# GCharger.net
KiCad netlist of a schematic drawn in EAGLE
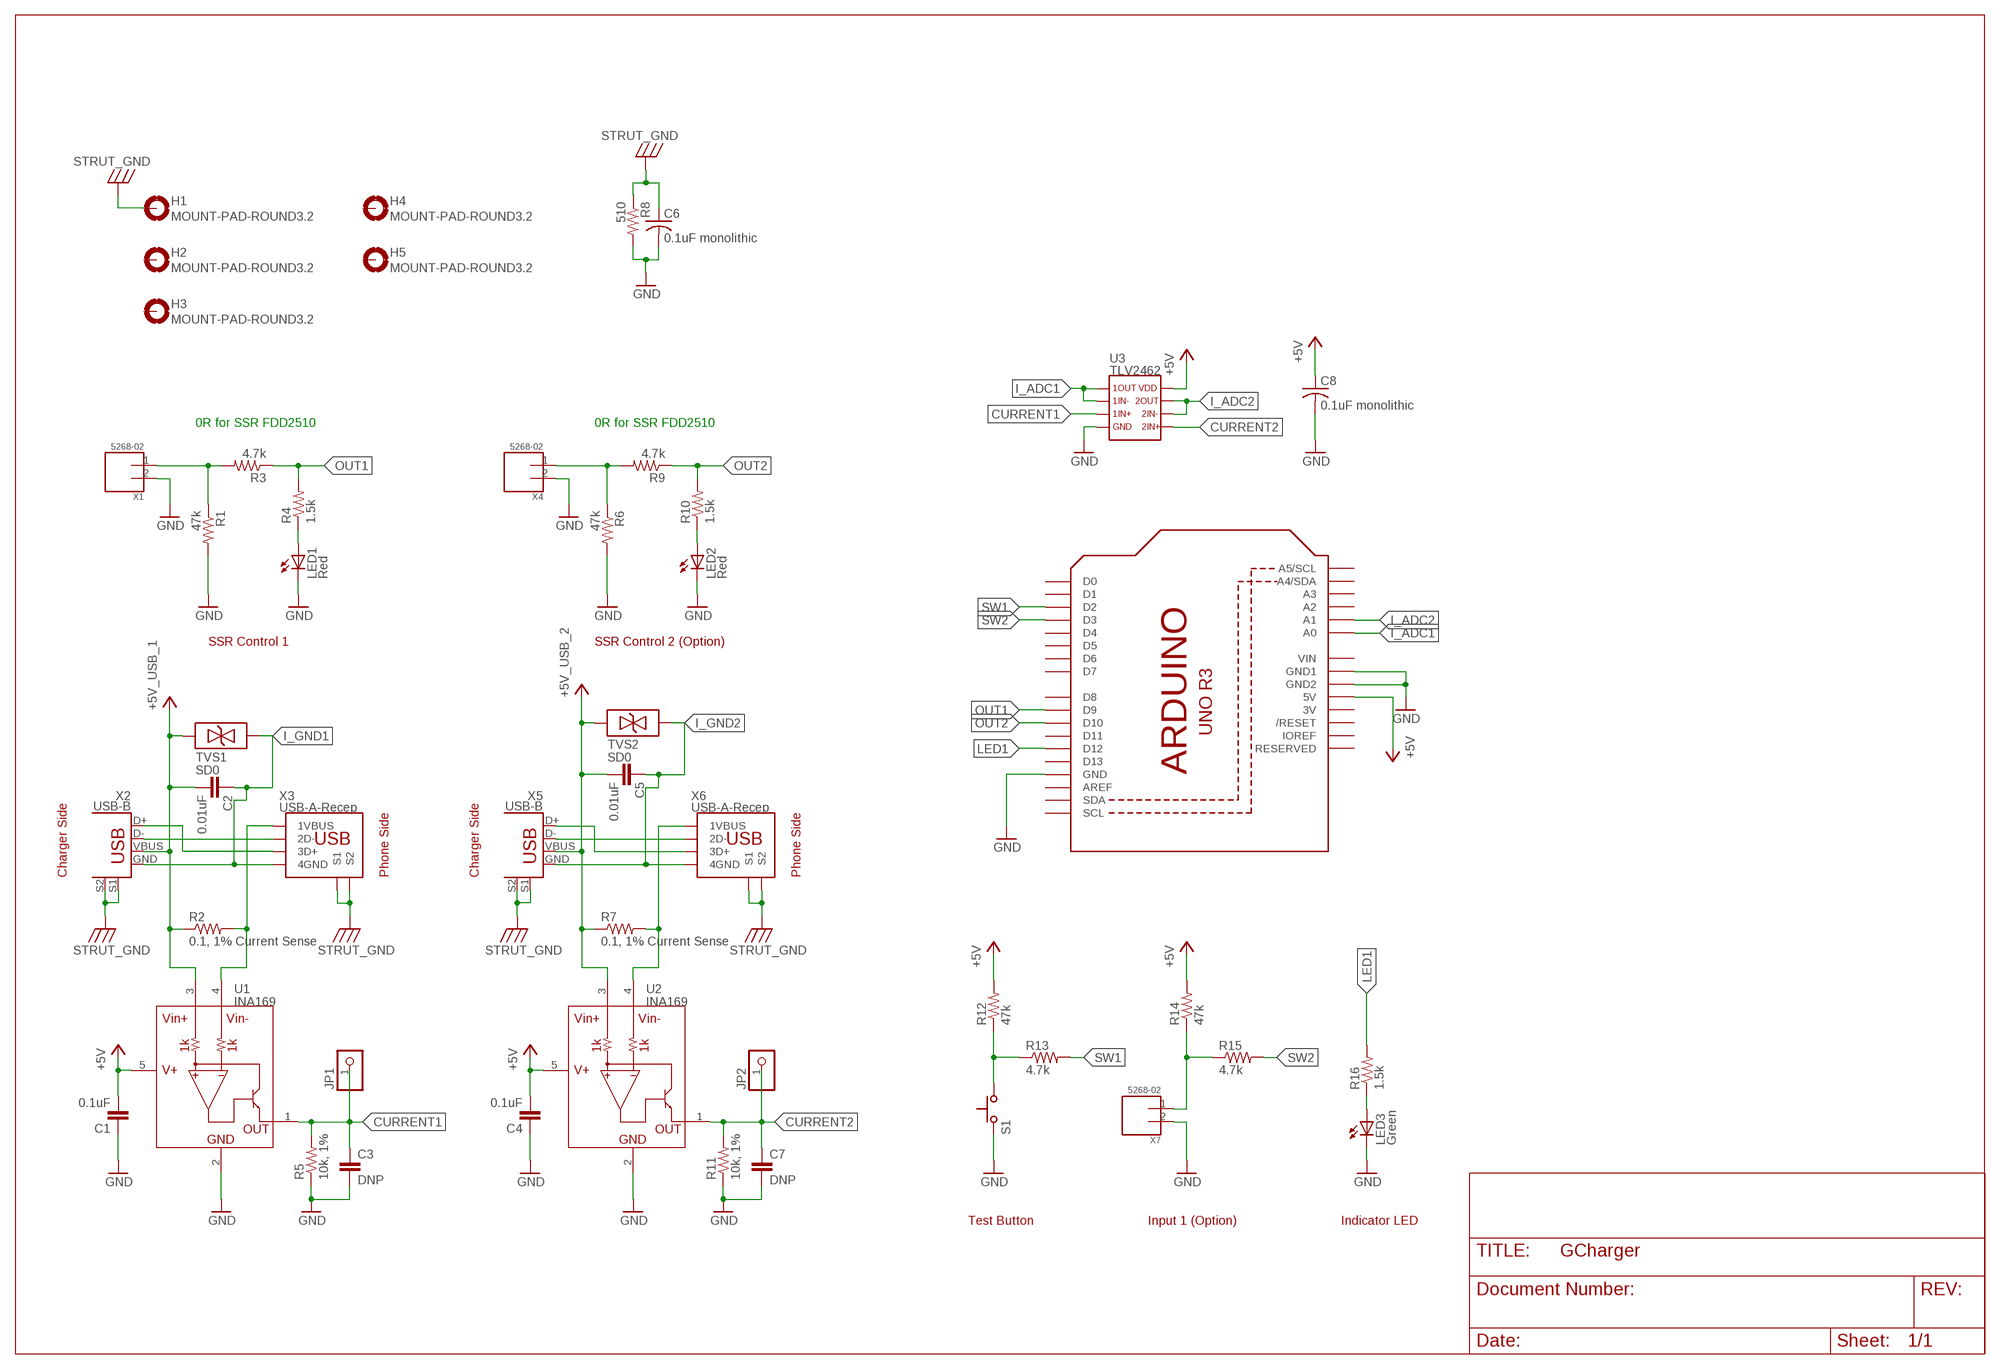
[diagram p0: schematic, sheet 1]

(export (version "E")
  (design (tool "Eeschema 10.0.6"))
  (components
    (comp (ref "C1")
      (value "0.1uF")
      (footprint "eagle-import:C0603(1608)")
      (libsource (lib "eagle-import") (part "C0603(1608)"))
    )
    (comp (ref "C2")
      (value "0.01uF")
      (footprint "eagle-import:C0603(1608)")
      (libsource (lib "eagle-import") (part "C0603(1608)"))
    )
    (comp (ref "C3")
      (value "DNP")
      (footprint "eagle-import:C0603(1608)")
      (libsource (lib "eagle-import") (part "g-project_C0603(1608)"))
    )
    (comp (ref "C4")
      (value "0.1uF")
      (footprint "eagle-import:C0603(1608)")
      (libsource (lib "eagle-import") (part "C0603(1608)"))
    )
    (comp (ref "C5")
      (value "0.01uF")
      (footprint "eagle-import:C0603(1608)")
      (libsource (lib "eagle-import") (part "C0603(1608)"))
    )
    (comp (ref "C6")
      (value "0.1uF monolithic")
      (footprint "eagle-import:C050-024X044")
      (libsource (lib "eagle-import") (part "C-US050-024X044"))
    )
    (comp (ref "C7")
      (value "DNP")
      (footprint "eagle-import:C0603(1608)")
      (libsource (lib "eagle-import") (part "g-project_C0603(1608)"))
    )
    (comp (ref "C8")
      (value "0.1uF monolithic")
      (footprint "eagle-import:C050-024X044")
      (libsource (lib "eagle-import") (part "C-US050-024X044"))
    )
    (comp (ref "H1")
      (value "MOUNT-PAD-ROUND3.2")
      (footprint "eagle-import:3.2-PAD-ROUND")
      (libsource (lib "eagle-import") (part "MOUNT-PAD-ROUND3.2"))
    )
    (comp (ref "H2")
      (value "MOUNT-PAD-ROUND3.2")
      (footprint "eagle-import:3.2-PAD-ROUND")
      (libsource (lib "eagle-import") (part "MOUNT-PAD-ROUND3.2"))
    )
    (comp (ref "H3")
      (value "MOUNT-PAD-ROUND3.2")
      (footprint "eagle-import:3.2-PAD-ROUND")
      (libsource (lib "eagle-import") (part "MOUNT-PAD-ROUND3.2"))
    )
    (comp (ref "H4")
      (value "MOUNT-PAD-ROUND3.2")
      (footprint "eagle-import:3.2-PAD-ROUND")
      (libsource (lib "eagle-import") (part "MOUNT-PAD-ROUND3.2"))
    )
    (comp (ref "H5")
      (value "MOUNT-PAD-ROUND3.2")
      (footprint "eagle-import:3.2-PAD-ROUND")
      (libsource (lib "eagle-import") (part "MOUNT-PAD-ROUND3.2"))
    )
    (comp (ref "JP1")
      (value "PINHD-1X1CB")
      (footprint "eagle-import:1X01-CLEANBIG")
      (libsource (lib "eagle-import") (part "PINHD-1X1CB"))
    )
    (comp (ref "JP2")
      (value "PINHD-1X1CB")
      (footprint "eagle-import:1X01-CLEANBIG")
      (libsource (lib "eagle-import") (part "PINHD-1X1CB"))
    )
    (comp (ref "LED1")
      (value "Red")
      (footprint "eagle-import:LED3MM")
      (libsource (lib "eagle-import") (part "LED3MM"))
    )
    (comp (ref "LED2")
      (value "Red")
      (footprint "eagle-import:LED3MM")
      (libsource (lib "eagle-import") (part "LED3MM"))
    )
    (comp (ref "LED3")
      (value "Green")
      (footprint "eagle-import:LED3MM")
      (libsource (lib "eagle-import") (part "LED3MM"))
    )
    (comp (ref "R1")
      (value "47k")
      (footprint "eagle-import:0805-THM")
      (libsource (lib "eagle-import") (part "R-US_FLIPFLOP"))
    )
    (comp (ref "R2")
      (value "0.1, 1% Current Sense")
      (footprint "eagle-import:1206")
      (libsource (lib "eagle-import") (part "RESISTOR1206"))
    )
    (comp (ref "R3")
      (value "4.7k")
      (footprint "eagle-import:0805-THM")
      (libsource (lib "eagle-import") (part "R-US_FLIPFLOP"))
    )
    (comp (ref "R4")
      (value "1.5k")
      (footprint "eagle-import:0805-THM")
      (libsource (lib "eagle-import") (part "R-US_FLIPFLOP"))
    )
    (comp (ref "R5")
      (value "10k, 1%")
      (footprint "eagle-import:0805-THM")
      (libsource (lib "eagle-import") (part "R-US_FLIPFLOP"))
    )
    (comp (ref "R6")
      (value "47k")
      (footprint "eagle-import:0805-THM")
      (libsource (lib "eagle-import") (part "R-US_FLIPFLOP"))
    )
    (comp (ref "R7")
      (value "0.1, 1% Current Sense")
      (footprint "eagle-import:1206")
      (libsource (lib "eagle-import") (part "RESISTOR1206"))
    )
    (comp (ref "R8")
      (value "510")
      (footprint "eagle-import:0805-THM")
      (libsource (lib "eagle-import") (part "R-US_FLIPFLOP"))
    )
    (comp (ref "R9")
      (value "4.7k")
      (footprint "eagle-import:0805-THM")
      (libsource (lib "eagle-import") (part "R-US_FLIPFLOP"))
    )
    (comp (ref "R10")
      (value "1.5k")
      (footprint "eagle-import:0805-THM")
      (libsource (lib "eagle-import") (part "R-US_FLIPFLOP"))
    )
    (comp (ref "R11")
      (value "10k, 1%")
      (footprint "eagle-import:0805-THM")
      (libsource (lib "eagle-import") (part "R-US_FLIPFLOP"))
    )
    (comp (ref "R12")
      (value "47k")
      (footprint "eagle-import:0805-THM")
      (libsource (lib "eagle-import") (part "R-US_FLIPFLOP"))
    )
    (comp (ref "R13")
      (value "4.7k")
      (footprint "eagle-import:0805-THM")
      (libsource (lib "eagle-import") (part "R-US_FLIPFLOP"))
    )
    (comp (ref "R14")
      (value "47k")
      (footprint "eagle-import:0805-THM")
      (libsource (lib "eagle-import") (part "R-US_FLIPFLOP"))
    )
    (comp (ref "R15")
      (value "4.7k")
      (footprint "eagle-import:0805-THM")
      (libsource (lib "eagle-import") (part "R-US_FLIPFLOP"))
    )
    (comp (ref "R16")
      (value "1.5k")
      (footprint "eagle-import:0805-THM")
      (libsource (lib "eagle-import") (part "R-US_FLIPFLOP"))
    )
    (comp (ref "S1")
      (value "SWITCH")
      (footprint "eagle-import:SKHLACA010")
      (libsource (lib "eagle-import") (part "SWITCH"))
    )
    (comp (ref "TVS1")
      (value "SD0")
      (footprint "eagle-import:SOD-323")
      (libsource (lib "eagle-import") (part "SD0"))
    )
    (comp (ref "TVS2")
      (value "SD0")
      (footprint "eagle-import:SOD-323")
      (libsource (lib "eagle-import") (part "SD0"))
    )
    (comp (ref "U1")
      (value "INA169")
      (footprint "eagle-import:SOT23-5")
      (libsource (lib "eagle-import") (part "INA169"))
    )
    (comp (ref "U2")
      (value "INA169")
      (footprint "eagle-import:SOT23-5")
      (libsource (lib "eagle-import") (part "INA169"))
    )
    (comp (ref "U3")
      (value "TLV2462")
      (footprint "eagle-import:SO8")
      (libsource (lib "eagle-import") (part "TLV2462"))
    )
    (comp (ref "U4")
      (value "ARDUINOR3-TPLACE")
      (footprint "eagle-import:ARDUINOR3")
      (libsource (lib "eagle-import") (part "ARDUINOR3-TPLACE"))
    )
    (comp (ref "X1")
      (value "5268-02")
      (footprint "eagle-import:5628-02")
      (libsource (lib "eagle-import") (part "5268-02"))
    )
    (comp (ref "X2")
      (value "USB-B")
      (footprint "eagle-import:USB-B-PTH")
      (libsource (lib "eagle-import") (part "USB+SHIELD"))
    )
    (comp (ref "X3")
      (value "USB-A-Recep")
      (footprint "eagle-import:USB-A-RECEPT")
      (libsource (lib "eagle-import") (part "USB-787616"))
    )
    (comp (ref "X4")
      (value "5268-02")
      (footprint "eagle-import:5628-02")
      (libsource (lib "eagle-import") (part "5268-02"))
    )
    (comp (ref "X5")
      (value "USB-B")
      (footprint "eagle-import:USB-B-PTH")
      (libsource (lib "eagle-import") (part "USB+SHIELD"))
    )
    (comp (ref "X6")
      (value "USB-A-Recep")
      (footprint "eagle-import:USB-A-RECEPT")
      (libsource (lib "eagle-import") (part "USB-787616"))
    )
    (comp (ref "X7")
      (value "5268-02")
      (footprint "eagle-import:5628-02")
      (libsource (lib "eagle-import") (part "5268-02"))
    )
  )
  (nets
    (net (code "1") (name "+5V") (class "Default")
      (node (ref "C1") (pin "2") (pinfunction "2_2") (pintype "passive"))
      (node (ref "C4") (pin "2") (pinfunction "2_2") (pintype "passive"))
      (node (ref "C8") (pin "1") (pinfunction "1_1") (pintype "passive"))
      (node (ref "R12") (pin "2") (pinfunction "2_2") (pintype "passive"))
      (node (ref "R14") (pin "2") (pinfunction "2_2") (pintype "passive"))
      (node (ref "U1") (pin "5") (pinfunction "V+_5") (pintype "bidirectional"))
      (node (ref "U2") (pin "5") (pinfunction "V+_5") (pintype "bidirectional"))
      (node (ref "U3") (pin "8") (pinfunction "P$8_8") (pintype "bidirectional"))
      (node (ref "U4") (pin "5V") (pinfunction "5V_5V") (pintype "power_in"))
    )
    (net (code "2") (name "+5V_USB_1") (class "Default")
      (node (ref "C2") (pin "2") (pinfunction "2_2") (pintype "passive"))
      (node (ref "R2") (pin "1") (pinfunction "1_1") (pintype "passive"))
      (node (ref "TVS1") (pin "1") (pinfunction "P$1_1") (pintype "bidirectional"))
      (node (ref "U1") (pin "3") (pinfunction "VIN+_3") (pintype "bidirectional"))
      (node (ref "X2") (pin "VBUS") (pinfunction "VBUS_VBUS") (pintype "bidirectional"))
    )
    (net (code "3") (name "+5V_USB_2") (class "Default")
      (node (ref "C5") (pin "2") (pinfunction "2_2") (pintype "passive"))
      (node (ref "R7") (pin "1") (pinfunction "1_1") (pintype "passive"))
      (node (ref "TVS2") (pin "1") (pinfunction "P$1_1") (pintype "bidirectional"))
      (node (ref "U2") (pin "3") (pinfunction "VIN+_3") (pintype "bidirectional"))
      (node (ref "X5") (pin "VBUS") (pinfunction "VBUS_VBUS") (pintype "bidirectional"))
    )
    (net (code "4") (name "/3V") (class "Default")
      (node (ref "U4") (pin "3V") (pinfunction "3V_3V") (pintype "power_in"))
    )
    (net (code "5") (name "/VIN") (class "Default")
      (node (ref "U4") (pin "VIN") (pinfunction "VIN_VIN") (pintype "power_in"))
    )
    (net (code "6") (name "CURRENT1") (class "Default")
      (node (ref "C3") (pin "1") (pinfunction "1_1") (pintype "passive"))
      (node (ref "JP1") (pin "1") (pinfunction "1_1") (pintype "passive"))
      (node (ref "R5") (pin "2") (pinfunction "2_2") (pintype "passive"))
      (node (ref "U1") (pin "1") (pinfunction "OUT_1") (pintype "bidirectional"))
      (node (ref "U3") (pin "3") (pinfunction "P$3_3") (pintype "bidirectional"))
    )
    (net (code "7") (name "CURRENT2") (class "Default")
      (node (ref "C7") (pin "1") (pinfunction "1_1") (pintype "passive"))
      (node (ref "JP2") (pin "1") (pinfunction "1_1") (pintype "passive"))
      (node (ref "R11") (pin "2") (pinfunction "2_2") (pintype "passive"))
      (node (ref "U2") (pin "1") (pinfunction "OUT_1") (pintype "bidirectional"))
      (node (ref "U3") (pin "5") (pinfunction "P$5_5") (pintype "bidirectional"))
    )
    (net (code "8") (name "GND") (class "Default")
      (node (ref "C1") (pin "1") (pinfunction "1_1") (pintype "passive"))
      (node (ref "C3") (pin "2") (pinfunction "2_2") (pintype "passive"))
      (node (ref "C4") (pin "1") (pinfunction "1_1") (pintype "passive"))
      (node (ref "C6") (pin "2") (pinfunction "2_2") (pintype "passive"))
      (node (ref "C7") (pin "2") (pinfunction "2_2") (pintype "passive"))
      (node (ref "C8") (pin "2") (pinfunction "2_2") (pintype "passive"))
      (node (ref "LED1") (pin "K") (pinfunction "C_K") (pintype "passive"))
      (node (ref "LED2") (pin "K") (pinfunction "C_K") (pintype "passive"))
      (node (ref "LED3") (pin "K") (pinfunction "C_K") (pintype "passive"))
      (node (ref "R1") (pin "2") (pinfunction "2_2") (pintype "passive"))
      (node (ref "R11") (pin "1") (pinfunction "1_1") (pintype "passive"))
      (node (ref "R5") (pin "1") (pinfunction "1_1") (pintype "passive"))
      (node (ref "R6") (pin "2") (pinfunction "2_2") (pintype "passive"))
      (node (ref "R8") (pin "2") (pinfunction "2_2") (pintype "passive"))
      (node (ref "S1") (pin "P$1") (pinfunction "P$1_P$1") (pintype "bidirectional"))
      (node (ref "U1") (pin "2") (pinfunction "GND_2") (pintype "bidirectional"))
      (node (ref "U2") (pin "2") (pinfunction "GND_2") (pintype "bidirectional"))
      (node (ref "U3") (pin "4") (pinfunction "P$4_4") (pintype "bidirectional"))
      (node (ref "U4") (pin "GND") (pinfunction "GND_GND") (pintype "power_in"))
      (node (ref "U4") (pin "GND1") (pinfunction "GND1_GND1") (pintype "power_in"))
      (node (ref "U4") (pin "GND2") (pinfunction "GND2_GND2") (pintype "power_in"))
      (node (ref "X1") (pin "2") (pinfunction "2_2") (pintype "bidirectional"))
      (node (ref "X4") (pin "2") (pinfunction "2_2") (pintype "bidirectional"))
      (node (ref "X7") (pin "2") (pinfunction "2_2") (pintype "bidirectional"))
    )
    (net (code "9") (name "I_ADC1") (class "Default")
      (node (ref "U3") (pin "1") (pinfunction "P$1_1") (pintype "bidirectional"))
      (node (ref "U3") (pin "2") (pinfunction "P$2_2") (pintype "bidirectional"))
      (node (ref "U4") (pin "A0") (pinfunction "A0_A0") (pintype "bidirectional"))
    )
    (net (code "10") (name "I_ADC2") (class "Default")
      (node (ref "U3") (pin "6") (pinfunction "P$6_6") (pintype "bidirectional"))
      (node (ref "U3") (pin "7") (pinfunction "P$7_7") (pintype "bidirectional"))
      (node (ref "U4") (pin "A1") (pinfunction "A1_A1") (pintype "bidirectional"))
    )
    (net (code "11") (name "I_GND1") (class "Default")
      (node (ref "C2") (pin "1") (pinfunction "1_1") (pintype "passive"))
      (node (ref "TVS1") (pin "2") (pinfunction "P$2_2") (pintype "bidirectional"))
      (node (ref "X2") (pin "GND") (pinfunction "GND_GND") (pintype "bidirectional"))
      (node (ref "X3") (pin "4") (pinfunction "4GND_4") (pintype "passive"))
    )
    (net (code "12") (name "I_GND2") (class "Default")
      (node (ref "C5") (pin "1") (pinfunction "1_1") (pintype "passive"))
      (node (ref "TVS2") (pin "2") (pinfunction "P$2_2") (pintype "bidirectional"))
      (node (ref "X5") (pin "GND") (pinfunction "GND_GND") (pintype "bidirectional"))
      (node (ref "X6") (pin "4") (pinfunction "4GND_4") (pintype "passive"))
    )
    (net (code "13") (name "LED1") (class "Default")
      (node (ref "R16") (pin "2") (pinfunction "2_2") (pintype "passive"))
      (node (ref "U4") (pin "D12") (pinfunction "D12_D12") (pintype "bidirectional"))
    )
    (net (code "14") (name "Net-(LED1-PadA)") (class "Default")
      (node (ref "LED1") (pin "A") (pinfunction "A_A") (pintype "passive"))
      (node (ref "R4") (pin "1") (pinfunction "1_1") (pintype "passive"))
    )
    (net (code "15") (name "Net-(LED2-PadA)") (class "Default")
      (node (ref "LED2") (pin "A") (pinfunction "A_A") (pintype "passive"))
      (node (ref "R10") (pin "1") (pinfunction "1_1") (pintype "passive"))
    )
    (net (code "16") (name "Net-(LED3-PadA)") (class "Default")
      (node (ref "LED3") (pin "A") (pinfunction "A_A") (pintype "passive"))
      (node (ref "R16") (pin "1") (pinfunction "1_1") (pintype "passive"))
    )
    (net (code "17") (name "Net-(R1-Pad1)") (class "Default")
      (node (ref "R1") (pin "1") (pinfunction "1_1") (pintype "passive"))
      (node (ref "R3") (pin "2") (pinfunction "2_2") (pintype "passive"))
      (node (ref "X1") (pin "1") (pinfunction "1_1") (pintype "bidirectional"))
    )
    (net (code "18") (name "Net-(R6-Pad1)") (class "Default")
      (node (ref "R6") (pin "1") (pinfunction "1_1") (pintype "passive"))
      (node (ref "R9") (pin "2") (pinfunction "2_2") (pintype "passive"))
      (node (ref "X4") (pin "1") (pinfunction "1_1") (pintype "bidirectional"))
    )
    (net (code "19") (name "Net-(R12-Pad1)") (class "Default")
      (node (ref "R12") (pin "1") (pinfunction "1_1") (pintype "passive"))
      (node (ref "R13") (pin "1") (pinfunction "1_1") (pintype "passive"))
      (node (ref "S1") (pin "P$2") (pinfunction "P$2_P$2") (pintype "bidirectional"))
    )
    (net (code "20") (name "Net-(R14-Pad1)") (class "Default")
      (node (ref "R14") (pin "1") (pinfunction "1_1") (pintype "passive"))
      (node (ref "R15") (pin "1") (pinfunction "1_1") (pintype "passive"))
      (node (ref "X7") (pin "1") (pinfunction "1_1") (pintype "bidirectional"))
    )
    (net (code "21") (name "Net-(U1-VIN-)") (class "Default")
      (node (ref "R2") (pin "2") (pinfunction "2_2") (pintype "passive"))
      (node (ref "U1") (pin "4") (pinfunction "VIN-_4") (pintype "bidirectional"))
      (node (ref "X3") (pin "1") (pinfunction "1VBUS_1") (pintype "passive"))
    )
    (net (code "22") (name "Net-(U2-VIN-)") (class "Default")
      (node (ref "R7") (pin "2") (pinfunction "2_2") (pintype "passive"))
      (node (ref "U2") (pin "4") (pinfunction "VIN-_4") (pintype "bidirectional"))
      (node (ref "X6") (pin "1") (pinfunction "1VBUS_1") (pintype "passive"))
    )
    (net (code "23") (name "Net-(X3-2D-)") (class "Default")
      (node (ref "X2") (pin "D-") (pinfunction "D-_D-") (pintype "bidirectional"))
      (node (ref "X3") (pin "2") (pinfunction "2D-_2") (pintype "passive"))
    )
    (net (code "24") (name "Net-(X3-3D+)") (class "Default")
      (node (ref "X2") (pin "D+") (pinfunction "D+_D+") (pintype "bidirectional"))
      (node (ref "X3") (pin "3") (pinfunction "3D+_3") (pintype "passive"))
    )
    (net (code "25") (name "Net-(X6-2D-)") (class "Default")
      (node (ref "X5") (pin "D-") (pinfunction "D-_D-") (pintype "bidirectional"))
      (node (ref "X6") (pin "2") (pinfunction "2D-_2") (pintype "passive"))
    )
    (net (code "26") (name "Net-(X6-3D+)") (class "Default")
      (node (ref "X5") (pin "D+") (pinfunction "D+_D+") (pintype "bidirectional"))
      (node (ref "X6") (pin "3") (pinfunction "3D+_3") (pintype "passive"))
    )
    (net (code "27") (name "OUT1") (class "Default")
      (node (ref "R3") (pin "1") (pinfunction "1_1") (pintype "passive"))
      (node (ref "R4") (pin "2") (pinfunction "2_2") (pintype "passive"))
      (node (ref "U4") (pin "D9") (pinfunction "D9_D9") (pintype "bidirectional"))
    )
    (net (code "28") (name "OUT2") (class "Default")
      (node (ref "R10") (pin "2") (pinfunction "2_2") (pintype "passive"))
      (node (ref "R9") (pin "1") (pinfunction "1_1") (pintype "passive"))
      (node (ref "U4") (pin "D10") (pinfunction "D10_D10") (pintype "bidirectional"))
    )
    (net (code "29") (name "STRUT_GND") (class "Default")
      (node (ref "C6") (pin "1") (pinfunction "1_1") (pintype "passive"))
      (node (ref "H1") (pin "B3,2") (pinfunction "MOUNT_B3,2") (pintype "passive"))
      (node (ref "R8") (pin "1") (pinfunction "1_1") (pintype "passive"))
      (node (ref "X2") (pin "S1") (pinfunction "S1_S1") (pintype "bidirectional"))
      (node (ref "X2") (pin "S2") (pinfunction "S2_S2") (pintype "bidirectional"))
      (node (ref "X3") (pin "S1") (pinfunction "S1_S1") (pintype "passive"))
      (node (ref "X3") (pin "S2") (pinfunction "S2_S2") (pintype "passive"))
      (node (ref "X5") (pin "S1") (pinfunction "S1_S1") (pintype "bidirectional"))
      (node (ref "X5") (pin "S2") (pinfunction "S2_S2") (pintype "bidirectional"))
      (node (ref "X6") (pin "S1") (pinfunction "S1_S1") (pintype "passive"))
      (node (ref "X6") (pin "S2") (pinfunction "S2_S2") (pintype "passive"))
    )
    (net (code "30") (name "SW1") (class "Default")
      (node (ref "R13") (pin "2") (pinfunction "2_2") (pintype "passive"))
      (node (ref "U4") (pin "D2") (pinfunction "D2_D2") (pintype "bidirectional"))
    )
    (net (code "31") (name "SW2") (class "Default")
      (node (ref "R15") (pin "2") (pinfunction "2_2") (pintype "passive"))
      (node (ref "U4") (pin "D3") (pinfunction "D3_D3") (pintype "bidirectional"))
    )
    (net (code "32") (name "unconnected-(H2-MOUNT-PadB3,2)") (class "Default")
      (node (ref "H2") (pin "B3,2") (pinfunction "MOUNT_B3,2") (pintype "passive"))
    )
    (net (code "33") (name "unconnected-(H3-MOUNT-PadB3,2)") (class "Default")
      (node (ref "H3") (pin "B3,2") (pinfunction "MOUNT_B3,2") (pintype "passive"))
    )
    (net (code "34") (name "unconnected-(H4-MOUNT-PadB3,2)") (class "Default")
      (node (ref "H4") (pin "B3,2") (pinfunction "MOUNT_B3,2") (pintype "passive"))
    )
    (net (code "35") (name "unconnected-(H5-MOUNT-PadB3,2)") (class "Default")
      (node (ref "H5") (pin "B3,2") (pinfunction "MOUNT_B3,2") (pintype "passive"))
    )
    (net (code "36") (name "unconnected-(U4-A4{slash}SDA-PadA4)") (class "Default")
      (node (ref "U4") (pin "A4") (pinfunction "A4/SDA_A4") (pintype "bidirectional"))
    )
    (net (code "37") (name "unconnected-(U4-A5{slash}SCL-PadA5)") (class "Default")
      (node (ref "U4") (pin "A5") (pinfunction "A5/SCL_A5") (pintype "bidirectional"))
    )
    (net (code "38") (name "unconnected-(U4-PadA2)") (class "Default")
      (node (ref "U4") (pin "A2") (pinfunction "A2_A2") (pintype "bidirectional"))
    )
    (net (code "39") (name "unconnected-(U4-PadA3)") (class "Default")
      (node (ref "U4") (pin "A3") (pinfunction "A3_A3") (pintype "bidirectional"))
    )
    (net (code "40") (name "unconnected-(U4-PadAREF)") (class "Default")
      (node (ref "U4") (pin "AREF") (pinfunction "AREF_AREF") (pintype "bidirectional"))
    )
    (net (code "41") (name "unconnected-(U4-PadD0)") (class "Default")
      (node (ref "U4") (pin "D0") (pinfunction "D0_D0") (pintype "bidirectional"))
    )
    (net (code "42") (name "unconnected-(U4-PadD1)") (class "Default")
      (node (ref "U4") (pin "D1") (pinfunction "D1_D1") (pintype "bidirectional"))
    )
    (net (code "43") (name "unconnected-(U4-PadD4)") (class "Default")
      (node (ref "U4") (pin "D4") (pinfunction "D4_D4") (pintype "bidirectional"))
    )
    (net (code "44") (name "unconnected-(U4-PadD5)") (class "Default")
      (node (ref "U4") (pin "D5") (pinfunction "D5_D5") (pintype "bidirectional"))
    )
    (net (code "45") (name "unconnected-(U4-PadD6)") (class "Default")
      (node (ref "U4") (pin "D6") (pinfunction "D6_D6") (pintype "bidirectional"))
    )
    (net (code "46") (name "unconnected-(U4-PadD7)") (class "Default")
      (node (ref "U4") (pin "D7") (pinfunction "D7_D7") (pintype "bidirectional"))
    )
    (net (code "47") (name "unconnected-(U4-PadD8)") (class "Default")
      (node (ref "U4") (pin "D8") (pinfunction "D8_D8") (pintype "bidirectional"))
    )
    (net (code "48") (name "unconnected-(U4-PadD11)") (class "Default")
      (node (ref "U4") (pin "D11") (pinfunction "D11_D11") (pintype "bidirectional"))
    )
    (net (code "49") (name "unconnected-(U4-PadD13)") (class "Default")
      (node (ref "U4") (pin "D13") (pinfunction "D13_D13") (pintype "bidirectional"))
    )
    (net (code "50") (name "unconnected-(U4-PadIOREF)") (class "Default")
      (node (ref "U4") (pin "IOREF") (pinfunction "IOREF_IOREF") (pintype "output"))
    )
    (net (code "51") (name "unconnected-(U4-PadRESERVED)") (class "Default")
      (node (ref "U4") (pin "RESERVED") (pinfunction "RESERVED_RESERVED") (pintype "no_connect"))
    )
    (net (code "52") (name "unconnected-(U4-PadSCL)") (class "Default")
      (node (ref "U4") (pin "SCL") (pinfunction "SCL_SCL") (pintype "bidirectional"))
    )
    (net (code "53") (name "unconnected-(U4-PadSDA)") (class "Default")
      (node (ref "U4") (pin "SDA") (pinfunction "SDA_SDA") (pintype "bidirectional"))
    )
    (net (code "54") (name "unconnected-(U4-{slash}RESET-PadRESET)") (class "Default")
      (node (ref "U4") (pin "RESET") (pinfunction "/RESET_RESET") (pintype "bidirectional"))
    )
  )
)
